# Connections.net
KiCad netlist of a schematic drawn in Altium Designer
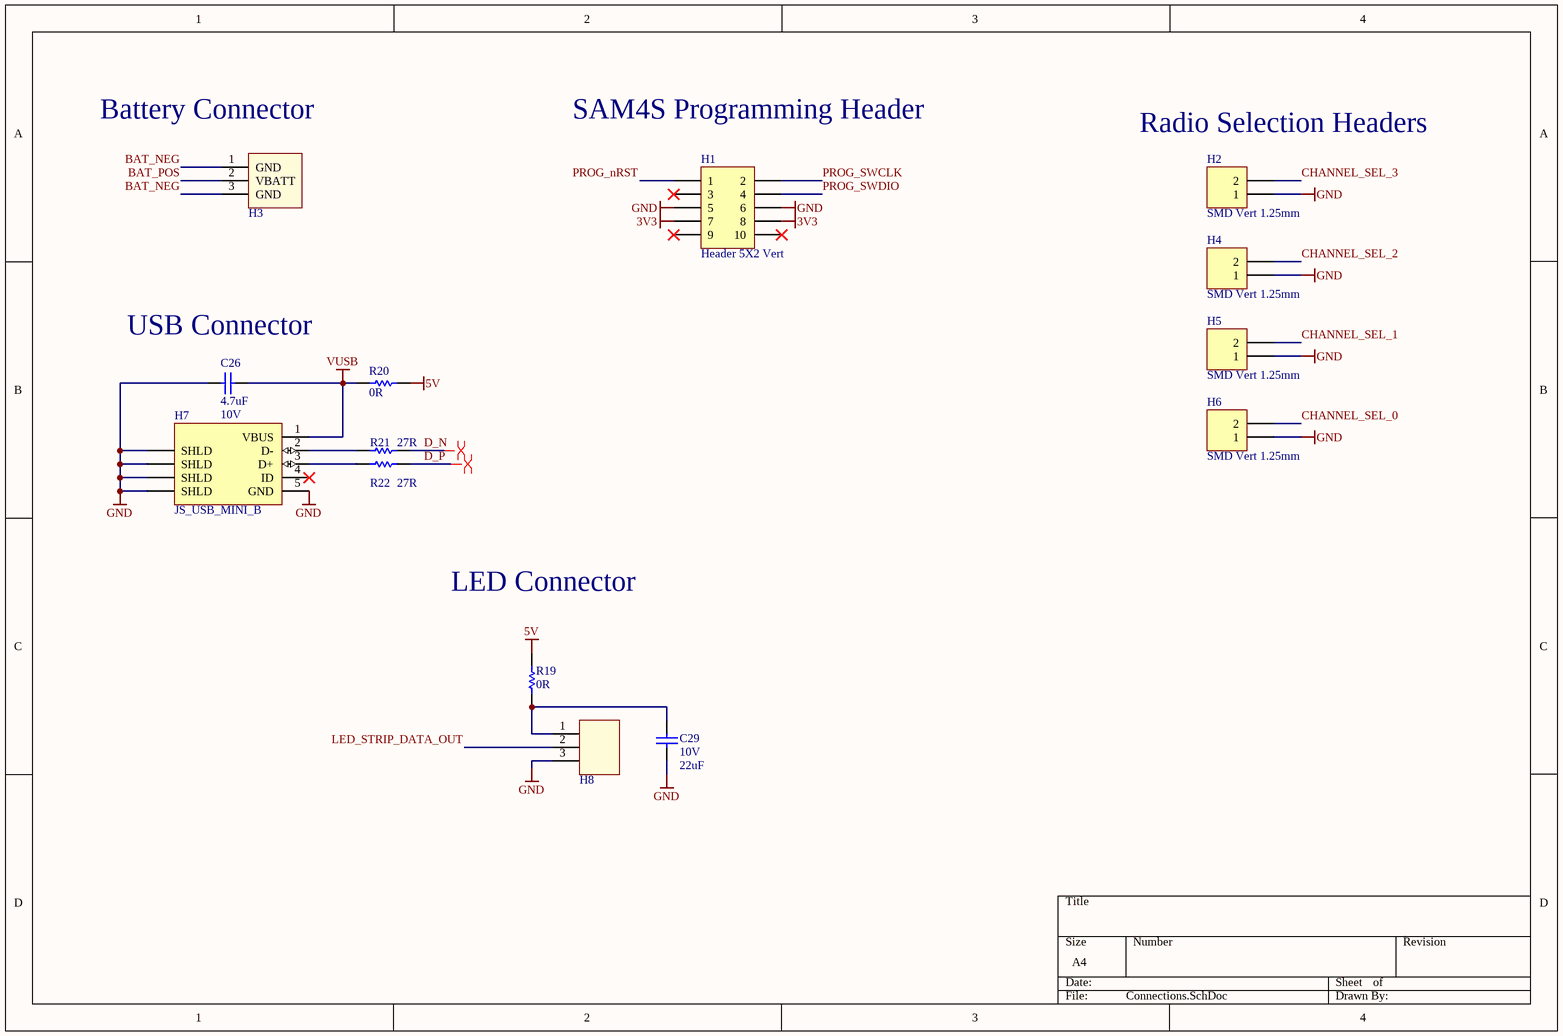
[diagram p0: Connections.SchDoc]

(export (version "E")
  (design (tool "Eeschema 10.0.6"))
  (components
    (comp (ref "C26")
      (value "4.7uF")
      (footprint "CAPC1608N")
      (description "CAP CER 4.7uF X5R +-20%  10V 0603")
      (fields (field (name "MAX VOLTAGE") "10V"))
      (libsource (lib "ECE AD19Components_19V1") (part "CC_4.7uF_0603"))
    )
    (comp (ref "C29")
      (value "22uF")
      (footprint "CAPC3216L")
      (description "CAP CER 22uF Y5V -20% +80% 10V 1206")
      (fields (field (name "MAX VOLTAGE") "10V"))
      (libsource (lib "ECE AD19Components_19V1") (part "CC_22uF_1206"))
    )
    (comp (ref "H1")
      (value "Header 5X2 Vert")
      (footprint "IDC2.54-V10D")
      (description "IDC Header, 2,54mm, 10-Pin, Vert")
      (libsource (lib "ECE AD19Components_19V1") (part "JA_HDR_IDC_5X2_VERT"))
    )
    (comp (ref "H2")
      (value "SMD Vert 1.25mm")
      (footprint "SD-53398-0219")
      (description "Header_Vert_2Pos_1.25mm_125V@1A_SMT")
      (fields
        (field (name "MANUFACTURER") "Molex Inc")
        (field (name "MANUFACTURER PART NUMBER") "0533980271")
      )
      (libsource (lib "ECE AD19Components_19V1") (part "JB_53398-02"))
    )
    (comp (ref "H3")
      (value "Battery_HEADER_3pin")
      (footprint "BATT_HEADER_3POS")
      (description "3Pin Header 2.54mm spacing")
      (libsource (lib "ENCE461AD19_19V2") (part "Battery_HEADER_3pin"))
    )
    (comp (ref "H4")
      (value "SMD Vert 1.25mm")
      (footprint "SD-53398-0219")
      (description "Header_Vert_2Pos_1.25mm_125V@1A_SMT")
      (fields
        (field (name "MANUFACTURER") "Molex Inc")
        (field (name "MANUFACTURER PART NUMBER") "0533980271")
      )
      (libsource (lib "ECE AD19Components_19V1") (part "JB_53398-02"))
    )
    (comp (ref "H5")
      (value "SMD Vert 1.25mm")
      (footprint "SD-53398-0219")
      (description "Header_Vert_2Pos_1.25mm_125V@1A_SMT")
      (fields
        (field (name "MANUFACTURER") "Molex Inc")
        (field (name "MANUFACTURER PART NUMBER") "0533980271")
      )
      (libsource (lib "ECE AD19Components_19V1") (part "JB_53398-02"))
    )
    (comp (ref "H6")
      (value "SMD Vert 1.25mm")
      (footprint "SD-53398-0219")
      (description "Header_Vert_2Pos_1.25mm_125V@1A_SMT")
      (fields
        (field (name "MANUFACTURER") "Molex Inc")
        (field (name "MANUFACTURER PART NUMBER") "0533980271")
      )
      (libsource (lib "ECE AD19Components_19V1") (part "JB_53398-02"))
    )
    (comp (ref "H7")
      (value "JS_USB_MINI_B")
      (footprint "USB/SM0.8-6H5")
      (description "USB 2.0, Right Angle, SMT, B Type, Receptacle, 5 Position,")
      (fields (field (name "MANUFACTURER") "FCI"))
      (libsource (lib "ECE AD19Components_19V1") (part "JS_USB_MINI_B_SMT"))
    )
    (comp (ref "H8")
      (value "HEADER_3")
      (footprint "HEADER_3POS")
      (description "3Pin Header 2.54mm spacing")
      (libsource (lib "ENCE461AD19_19V2") (part "HEADER_3"))
    )
    (comp (ref "R19")
      (value "0R")
      (footprint "RESC1608L")
      (description "RES 0.0 OHM 1/10W 5% 0603 SMD")
      (libsource (lib "ECE AD19Components_19V1") (part "RS_0R0"))
    )
    (comp (ref "R20")
      (value "0R")
      (footprint "RESC1608L")
      (description "RES 0.0 OHM 1/10W 5% 0603 SMD")
      (libsource (lib "ECE AD19Components_19V1") (part "RS_0R0"))
    )
    (comp (ref "R21")
      (value "27R")
      (footprint "RESC1608L")
      (description "RES 27 OHM 1/10W 5% 0603 SMD")
      (libsource (lib "ECE AD19Components_19V1") (part "RS_27R"))
    )
    (comp (ref "R22")
      (value "27R")
      (footprint "RESC1608L")
      (description "RES 27 OHM 1/10W 5% 0603 SMD")
      (libsource (lib "ECE AD19Components_19V1") (part "RS_27R"))
    )
  )
  (nets
    (net (code "1") (name "/BAT_NEG") (class "Default")
      (node (ref "H3") (pin "1") (pinfunction "GND_1") (pintype "passive"))
      (node (ref "H3") (pin "3") (pinfunction "GND_3") (pintype "passive"))
    )
    (net (code "2") (name "/BAT_POS") (class "Default")
      (node (ref "H3") (pin "2") (pinfunction "VBATT_2") (pintype "passive"))
    )
    (net (code "3") (name "/CHANNEL_SEL_0") (class "Default")
      (node (ref "H6") (pin "2") (pinfunction "2_2") (pintype "passive"))
    )
    (net (code "4") (name "/CHANNEL_SEL_1") (class "Default")
      (node (ref "H5") (pin "2") (pinfunction "2_2") (pintype "passive"))
    )
    (net (code "5") (name "/CHANNEL_SEL_2") (class "Default")
      (node (ref "H4") (pin "2") (pinfunction "2_2") (pintype "passive"))
    )
    (net (code "6") (name "/CHANNEL_SEL_3") (class "Default")
      (node (ref "H2") (pin "2") (pinfunction "2_2") (pintype "passive"))
    )
    (net (code "7") (name "/D_N") (class "Default")
      (node (ref "R21") (pin "2") (pinfunction "2_2") (pintype "passive"))
    )
    (net (code "8") (name "/D_P") (class "Default")
      (node (ref "R22") (pin "2") (pinfunction "2_2") (pintype "passive"))
    )
    (net (code "9") (name "/LED_STRIP_DATA_OUT") (class "Default")
      (node (ref "H8") (pin "2") (pintype "passive"))
    )
    (net (code "10") (name "/PROG_SWCLK") (class "Default")
      (node (ref "H1") (pin "2") (pinfunction "2_2") (pintype "passive"))
    )
    (net (code "11") (name "/PROG_SWDIO") (class "Default")
      (node (ref "H1") (pin "4") (pinfunction "4_4") (pintype "passive"))
    )
    (net (code "12") (name "/PROG_nRST") (class "Default")
      (node (ref "H1") (pin "1") (pinfunction "1_1") (pintype "passive"))
    )
    (net (code "13") (name "3V3") (class "Default")
      (node (ref "H1") (pin "7") (pinfunction "7_7") (pintype "passive"))
      (node (ref "H1") (pin "8") (pinfunction "8_8") (pintype "passive"))
    )
    (net (code "14") (name "5V") (class "Default")
      (node (ref "R19") (pin "2") (pinfunction "2_2") (pintype "passive"))
      (node (ref "R20") (pin "2") (pinfunction "2_2") (pintype "passive"))
    )
    (net (code "15") (name "GND") (class "Default")
      (node (ref "C26") (pin "2") (pinfunction "2_2") (pintype "passive"))
      (node (ref "C29") (pin "1") (pinfunction "1_1") (pintype "passive"))
      (node (ref "H1") (pin "5") (pinfunction "5_5") (pintype "passive"))
      (node (ref "H1") (pin "6") (pinfunction "6_6") (pintype "passive"))
      (node (ref "H2") (pin "1") (pinfunction "1_1") (pintype "passive"))
      (node (ref "H4") (pin "1") (pinfunction "1_1") (pintype "passive"))
      (node (ref "H5") (pin "1") (pinfunction "1_1") (pintype "passive"))
      (node (ref "H6") (pin "1") (pinfunction "1_1") (pintype "passive"))
      (node (ref "H7") (pin "5") (pinfunction "GND_5") (pintype "passive"))
      (node (ref "H7") (pin "6") (pinfunction "SHLD_6") (pintype "passive"))
      (node (ref "H7") (pin "7") (pinfunction "SHLD_7") (pintype "passive"))
      (node (ref "H7") (pin "8") (pinfunction "SHLD_8") (pintype "passive"))
      (node (ref "H7") (pin "9") (pinfunction "SHLD_9") (pintype "passive"))
      (node (ref "H8") (pin "3") (pintype "passive"))
    )
    (net (code "16") (name "Net-(C29-Pad2)") (class "Default")
      (node (ref "C29") (pin "2") (pinfunction "2_2") (pintype "passive"))
      (node (ref "H8") (pin "1") (pintype "passive"))
      (node (ref "R19") (pin "1") (pinfunction "1_1") (pintype "passive"))
    )
    (net (code "17") (name "Net-(H7-D+)") (class "Default")
      (node (ref "H7") (pin "3") (pinfunction "D+_3") (pintype "bidirectional"))
      (node (ref "R22") (pin "1") (pinfunction "1_1") (pintype "passive"))
    )
    (net (code "18") (name "Net-(H7-D-)") (class "Default")
      (node (ref "H7") (pin "2") (pinfunction "D-_2") (pintype "bidirectional"))
      (node (ref "R21") (pin "1") (pinfunction "1_1") (pintype "passive"))
    )
    (net (code "19") (name "VUSB") (class "Default")
      (node (ref "C26") (pin "1") (pinfunction "1_1") (pintype "passive"))
      (node (ref "H7") (pin "1") (pinfunction "VBUS_1") (pintype "power_in"))
      (node (ref "R20") (pin "1") (pinfunction "1_1") (pintype "passive"))
    )
    (net (code "20") (name "unconnected-(H1-Pad3)") (class "Default")
      (node (ref "H1") (pin "3") (pinfunction "3_3") (pintype "passive+no_connect"))
    )
    (net (code "21") (name "unconnected-(H1-Pad9)") (class "Default")
      (node (ref "H1") (pin "9") (pinfunction "9_9") (pintype "passive+no_connect"))
    )
    (net (code "22") (name "unconnected-(H1-Pad10)") (class "Default")
      (node (ref "H1") (pin "10") (pinfunction "10_10") (pintype "passive+no_connect"))
    )
    (net (code "23") (name "unconnected-(H7-ID-Pad4)") (class "Default")
      (node (ref "H7") (pin "4") (pinfunction "ID_4") (pintype "power_in+no_connect"))
    )
  )
)
